# Arduino_PCD8544.net
KiCad netlist of a schematic drawn in EAGLE
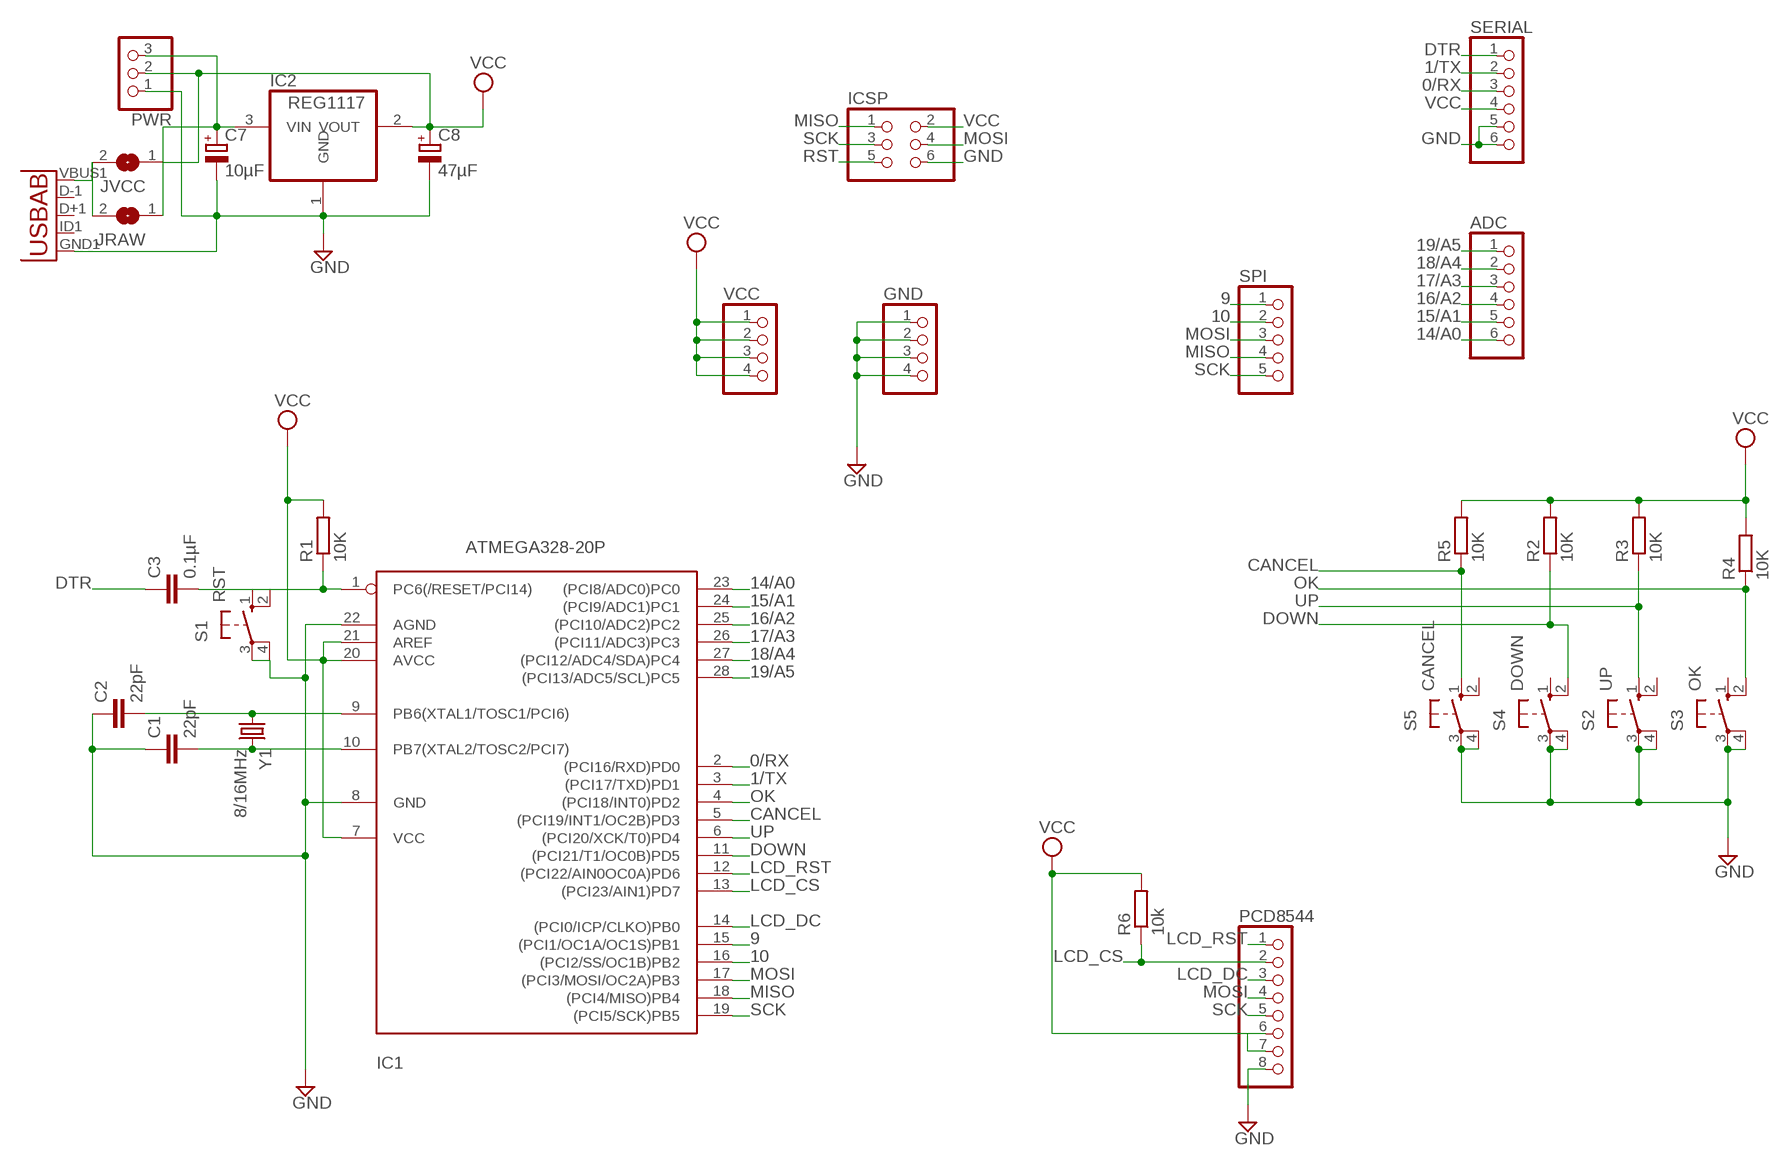
[diagram p0: schematic, sheet 1]

(export (version "E")
  (design (tool "Eeschema 10.0.6"))
  (components
    (comp (ref "ADC")
      (value "PINHD-1X6")
      (footprint "eagle-import:1X06")
      (libsource (lib "eagle-import") (part "PINHD-1X6"))
    )
    (comp (ref "C1")
      (value "22pF")
      (footprint "eagle-import:C0805")
      (libsource (lib "eagle-import") (part "C-EUC0805"))
    )
    (comp (ref "C2")
      (value "22pF")
      (footprint "eagle-import:C0805")
      (libsource (lib "eagle-import") (part "C-EUC0805"))
    )
    (comp (ref "C3")
      (value "0.1µF")
      (footprint "eagle-import:C0805")
      (libsource (lib "eagle-import") (part "C-EUC0805"))
    )
    (comp (ref "C7")
      (value "10µF")
      (footprint "eagle-import:E2,5-5")
      (libsource (lib "eagle-import") (part "CPOL-EUE2.5-5"))
    )
    (comp (ref "C8")
      (value "47µF")
      (footprint "eagle-import:E2,5-5")
      (libsource (lib "eagle-import") (part "CPOL-EUE2.5-5"))
    )
    (comp (ref "GND")
      (value "PINHD-1X4")
      (footprint "eagle-import:1X04")
      (libsource (lib "eagle-import") (part "PINHD-1X4"))
    )
    (comp (ref "IC1")
      (value "ATMEGA328-20P")
      (footprint "eagle-import:DIL28-3")
      (libsource (lib "eagle-import") (part "ATMEGA328P-20"))
    )
    (comp (ref "IC2")
      (value "REG1117")
      (footprint "eagle-import:SOT223")
      (libsource (lib "eagle-import") (part "REG1117"))
    )
    (comp (ref "ICSP")
      (value "PINHD-2X3")
      (footprint "eagle-import:2X03")
      (libsource (lib "eagle-import") (part "PINHD-2X3"))
    )
    (comp (ref "JRAW")
      (value "SJ")
      (footprint "eagle-import:SJ")
      (libsource (lib "eagle-import") (part "SJ"))
    )
    (comp (ref "JVCC")
      (value "SJ")
      (footprint "eagle-import:SJ")
      (libsource (lib "eagle-import") (part "SJ"))
    )
    (comp (ref "PCD8544")
      (value "PINHD-1X8")
      (footprint "eagle-import:1X08")
      (libsource (lib "eagle-import") (part "PINHD-1X8"))
    )
    (comp (ref "PWR")
      (value "PINHD-1X3")
      (footprint "eagle-import:1X03")
      (libsource (lib "eagle-import") (part "PINHD-1X3"))
    )
    (comp (ref "R1")
      (value "10K")
      (footprint "eagle-import:R0805")
      (libsource (lib "eagle-import") (part "R-EU_R0805"))
    )
    (comp (ref "R2")
      (value "10K")
      (footprint "eagle-import:R0805")
      (libsource (lib "eagle-import") (part "resistor_R-EU_R0805"))
    )
    (comp (ref "R3")
      (value "10K")
      (footprint "eagle-import:R0805")
      (libsource (lib "eagle-import") (part "resistor_R-EU_R0805"))
    )
    (comp (ref "R4")
      (value "10K")
      (footprint "eagle-import:R0805")
      (libsource (lib "eagle-import") (part "resistor_R-EU_R0805"))
    )
    (comp (ref "R5")
      (value "10K")
      (footprint "eagle-import:R0805")
      (libsource (lib "eagle-import") (part "resistor_R-EU_R0805"))
    )
    (comp (ref "R6")
      (value "10k")
      (footprint "eagle-import:R0805")
      (libsource (lib "eagle-import") (part "resistor_R-EU_R0805"))
    )
    (comp (ref "S1")
      (value "RST")
      (footprint "eagle-import:B3F-10XX")
      (fields (field (name "MPN") "B3F-1000"))
      (libsource (lib "eagle-import") (part "10-XX"))
    )
    (comp (ref "S2")
      (value "UP")
      (footprint "eagle-import:B3F-10XX")
      (fields (field (name "MPN") "B3F-1000"))
      (libsource (lib "eagle-import") (part "10-XX"))
    )
    (comp (ref "S3")
      (value "OK")
      (footprint "eagle-import:B3F-10XX")
      (fields (field (name "MPN") "B3F-1000"))
      (libsource (lib "eagle-import") (part "10-XX"))
    )
    (comp (ref "S4")
      (value "DOWN")
      (footprint "eagle-import:B3F-10XX")
      (fields (field (name "MPN") "B3F-1000"))
      (libsource (lib "eagle-import") (part "10-XX"))
    )
    (comp (ref "S5")
      (value "CANCEL")
      (footprint "eagle-import:B3F-10XX")
      (fields (field (name "MPN") "B3F-1000"))
      (libsource (lib "eagle-import") (part "10-XX"))
    )
    (comp (ref "SERIAL")
      (value "PINHD-1X6")
      (footprint "eagle-import:1X06")
      (libsource (lib "eagle-import") (part "PINHD-1X6"))
    )
    (comp (ref "SPI")
      (value "PINHD-1X5")
      (footprint "eagle-import:1X05")
      (libsource (lib "eagle-import") (part "PINHD-1X5"))
    )
    (comp (ref "U1")
      (value "USB\"\"")
      (footprint "eagle-import:USB-MICRO-SMD")
      (libsource (lib "eagle-import") (part "USB{dblquote}{dblquote}"))
    )
    (comp (ref "VCC")
      (value "PINHD-1X4")
      (footprint "eagle-import:1X04")
      (libsource (lib "eagle-import") (part "PINHD-1X4"))
    )
    (comp (ref "Y1")
      (value "8/16MHz")
      (footprint "eagle-import:HC49US")
      (libsource (lib "eagle-import") (part "CRYSTALHC49US"))
    )
  )
  (nets
    (net (code "1") (name "/0{slash}RX") (class "Default")
      (node (ref "IC1") (pin "2") (pinfunction "(PCI16/RXD)PD0_2") (pintype "bidirectional"))
      (node (ref "SERIAL") (pin "3") (pinfunction "3_3") (pintype "passive"))
    )
    (net (code "2") (name "/1{slash}TX") (class "Default")
      (node (ref "IC1") (pin "3") (pinfunction "(PCI17/TXD)PD1_3") (pintype "bidirectional"))
      (node (ref "SERIAL") (pin "2") (pinfunction "2_2") (pintype "passive"))
    )
    (net (code "3") (name "/9") (class "Default")
      (node (ref "IC1") (pin "15") (pinfunction "(PCI1/OC1A/OC1S)PB1_15") (pintype "bidirectional"))
      (node (ref "SPI") (pin "1") (pinfunction "1_1") (pintype "passive"))
    )
    (net (code "4") (name "/10") (class "Default")
      (node (ref "IC1") (pin "16") (pinfunction "(PCI2/SS/OC1B)PB2_16") (pintype "bidirectional"))
      (node (ref "SPI") (pin "2") (pinfunction "2_2") (pintype "passive"))
    )
    (net (code "5") (name "/14{slash}A0") (class "Default")
      (node (ref "ADC") (pin "6") (pinfunction "6_6") (pintype "passive"))
      (node (ref "IC1") (pin "23") (pinfunction "(PCI8/ADC0)PC0_23") (pintype "bidirectional"))
    )
    (net (code "6") (name "/15{slash}A1") (class "Default")
      (node (ref "ADC") (pin "5") (pinfunction "5_5") (pintype "passive"))
      (node (ref "IC1") (pin "24") (pinfunction "(PCI9/ADC1)PC1_24") (pintype "bidirectional"))
    )
    (net (code "7") (name "/16{slash}A2") (class "Default")
      (node (ref "ADC") (pin "4") (pinfunction "4_4") (pintype "passive"))
      (node (ref "IC1") (pin "25") (pinfunction "(PCI10/ADC2)PC2_25") (pintype "bidirectional"))
    )
    (net (code "8") (name "/17{slash}A3") (class "Default")
      (node (ref "ADC") (pin "3") (pinfunction "3_3") (pintype "passive"))
      (node (ref "IC1") (pin "26") (pinfunction "(PCI11/ADC3)PC3_26") (pintype "bidirectional"))
    )
    (net (code "9") (name "/18{slash}A4") (class "Default")
      (node (ref "ADC") (pin "2") (pinfunction "2_2") (pintype "passive"))
      (node (ref "IC1") (pin "27") (pinfunction "(PCI12/ADC4/SDA)PC4_27") (pintype "bidirectional"))
    )
    (net (code "10") (name "/19{slash}A5") (class "Default")
      (node (ref "ADC") (pin "1") (pinfunction "1_1") (pintype "passive"))
      (node (ref "IC1") (pin "28") (pinfunction "(PCI13/ADC5/SCL)PC5_28") (pintype "bidirectional"))
    )
    (net (code "11") (name "/CANCEL") (class "Default")
      (node (ref "IC1") (pin "5") (pinfunction "(PCI19/INT1/OC2B)PD3_5") (pintype "bidirectional"))
      (node (ref "R5") (pin "1") (pinfunction "1_1") (pintype "passive"))
      (node (ref "S5") (pin "1") (pinfunction "S_1") (pintype "passive"))
    )
    (net (code "12") (name "/DOWN") (class "Default")
      (node (ref "IC1") (pin "11") (pinfunction "(PCI21/T1/OC0B)PD5_11") (pintype "bidirectional"))
      (node (ref "R2") (pin "1") (pinfunction "1_1") (pintype "passive"))
      (node (ref "S4") (pin "2") (pinfunction "S1_2") (pintype "passive"))
    )
    (net (code "13") (name "/DTR") (class "Default")
      (node (ref "C3") (pin "1") (pinfunction "1_1") (pintype "passive"))
      (node (ref "SERIAL") (pin "1") (pinfunction "1_1") (pintype "passive"))
    )
    (net (code "14") (name "/LCD_CS") (class "Default")
      (node (ref "IC1") (pin "13") (pinfunction "(PCI23/AIN1)PD7_13") (pintype "bidirectional"))
      (node (ref "PCD8544") (pin "2") (pinfunction "2_2") (pintype "passive"))
      (node (ref "R6") (pin "1") (pinfunction "1_1") (pintype "passive"))
    )
    (net (code "15") (name "/LCD_DC") (class "Default")
      (node (ref "IC1") (pin "14") (pinfunction "(PCI0/ICP/CLKO)PB0_14") (pintype "bidirectional"))
      (node (ref "PCD8544") (pin "3") (pinfunction "3_3") (pintype "passive"))
    )
    (net (code "16") (name "/LCD_RST") (class "Default")
      (node (ref "IC1") (pin "12") (pinfunction "(PCI22/AIN0OC0A)PD6_12") (pintype "bidirectional"))
      (node (ref "PCD8544") (pin "1") (pinfunction "1_1") (pintype "passive"))
    )
    (net (code "17") (name "/MISO") (class "Default")
      (node (ref "IC1") (pin "18") (pinfunction "(PCI4/MISO)PB4_18") (pintype "bidirectional"))
      (node (ref "ICSP") (pin "1") (pinfunction "1_1") (pintype "passive"))
      (node (ref "SPI") (pin "4") (pinfunction "4_4") (pintype "passive"))
    )
    (net (code "18") (name "/MOSI") (class "Default")
      (node (ref "IC1") (pin "17") (pinfunction "(PCI3/MOSI/OC2A)PB3_17") (pintype "bidirectional"))
      (node (ref "ICSP") (pin "4") (pinfunction "4_4") (pintype "passive"))
      (node (ref "PCD8544") (pin "4") (pinfunction "4_4") (pintype "passive"))
      (node (ref "SPI") (pin "3") (pinfunction "3_3") (pintype "passive"))
    )
    (net (code "19") (name "/OK") (class "Default")
      (node (ref "IC1") (pin "4") (pinfunction "(PCI18/INT0)PD2_4") (pintype "bidirectional"))
      (node (ref "R4") (pin "1") (pinfunction "1_1") (pintype "passive"))
      (node (ref "S3") (pin "2") (pinfunction "S1_2") (pintype "passive"))
    )
    (net (code "20") (name "/RST") (class "Default")
      (node (ref "C3") (pin "2") (pinfunction "2_2") (pintype "passive"))
      (node (ref "IC1") (pin "1") (pinfunction "PC6(/RESET/PCI14)_1") (pintype "bidirectional"))
      (node (ref "ICSP") (pin "5") (pinfunction "5_5") (pintype "passive"))
      (node (ref "R1") (pin "1") (pinfunction "1_1") (pintype "passive"))
      (node (ref "S1") (pin "1") (pinfunction "S_1") (pintype "passive"))
      (node (ref "S1") (pin "2") (pinfunction "S1_2") (pintype "passive"))
    )
    (net (code "21") (name "/SCK") (class "Default")
      (node (ref "IC1") (pin "19") (pinfunction "(PCI5/SCK)PB5_19") (pintype "bidirectional"))
      (node (ref "ICSP") (pin "3") (pinfunction "3_3") (pintype "passive"))
      (node (ref "PCD8544") (pin "5") (pinfunction "5_5") (pintype "passive"))
      (node (ref "SPI") (pin "5") (pinfunction "5_5") (pintype "passive"))
    )
    (net (code "22") (name "/UP") (class "Default")
      (node (ref "IC1") (pin "6") (pinfunction "(PCI20/XCK/T0)PD4_6") (pintype "bidirectional"))
      (node (ref "R3") (pin "1") (pinfunction "1_1") (pintype "passive"))
      (node (ref "S2") (pin "1") (pinfunction "S_1") (pintype "passive"))
    )
    (net (code "23") (name "GND") (class "Default")
      (node (ref "C1") (pin "1") (pinfunction "1_1") (pintype "passive"))
      (node (ref "C2") (pin "1") (pinfunction "1_1") (pintype "passive"))
      (node (ref "C7") (pin "-") (pinfunction "-_-") (pintype "passive"))
      (node (ref "C8") (pin "-") (pinfunction "-_-") (pintype "passive"))
      (node (ref "GND") (pin "1") (pinfunction "1_1") (pintype "passive"))
      (node (ref "GND") (pin "2") (pinfunction "2_2") (pintype "passive"))
      (node (ref "GND") (pin "3") (pinfunction "3_3") (pintype "passive"))
      (node (ref "GND") (pin "4") (pinfunction "4_4") (pintype "passive"))
      (node (ref "IC1") (pin "22") (pinfunction "AGND_22") (pintype "bidirectional"))
      (node (ref "IC1") (pin "8") (pinfunction "GND_8") (pintype "bidirectional"))
      (node (ref "IC2") (pin "1") (pinfunction "GND_1") (pintype "power_in"))
      (node (ref "ICSP") (pin "6") (pinfunction "6_6") (pintype "passive"))
      (node (ref "PCD8544") (pin "8") (pinfunction "8_8") (pintype "passive"))
      (node (ref "PWR") (pin "1") (pinfunction "1_1") (pintype "passive"))
      (node (ref "S1") (pin "3") (pinfunction "P_3") (pintype "passive"))
      (node (ref "S1") (pin "4") (pinfunction "P1_4") (pintype "passive"))
      (node (ref "S2") (pin "3") (pinfunction "P_3") (pintype "passive"))
      (node (ref "S2") (pin "4") (pinfunction "P1_4") (pintype "passive"))
      (node (ref "S3") (pin "3") (pinfunction "P_3") (pintype "passive"))
      (node (ref "S3") (pin "4") (pinfunction "P1_4") (pintype "passive"))
      (node (ref "S4") (pin "3") (pinfunction "P_3") (pintype "passive"))
      (node (ref "S4") (pin "4") (pinfunction "P1_4") (pintype "passive"))
      (node (ref "S5") (pin "3") (pinfunction "P_3") (pintype "passive"))
      (node (ref "S5") (pin "4") (pinfunction "P1_4") (pintype "passive"))
      (node (ref "SERIAL") (pin "5") (pinfunction "5_5") (pintype "passive"))
      (node (ref "SERIAL") (pin "6") (pinfunction "6_6") (pintype "passive"))
      (node (ref "U1") (pin "GND1") (pinfunction "GND_GND1") (pintype "bidirectional"))
    )
    (net (code "24") (name "Net-(IC1-PB6(XTAL1{slash}TOSC1{slash}PCI6))") (class "Default")
      (node (ref "C2") (pin "2") (pinfunction "2_2") (pintype "passive"))
      (node (ref "IC1") (pin "9") (pinfunction "PB6(XTAL1/TOSC1/PCI6)_9") (pintype "bidirectional"))
      (node (ref "Y1") (pin "1") (pinfunction "1_1") (pintype "passive"))
    )
    (net (code "25") (name "Net-(IC1-PB7(XTAL2{slash}TOSC2{slash}PCI7))") (class "Default")
      (node (ref "C1") (pin "2") (pinfunction "2_2") (pintype "passive"))
      (node (ref "IC1") (pin "10") (pinfunction "PB7(XTAL2/TOSC2/PCI7)_10") (pintype "bidirectional"))
      (node (ref "Y1") (pin "2") (pinfunction "2_2") (pintype "passive"))
    )
    (net (code "26") (name "Net-(IC2-VIN)") (class "Default")
      (node (ref "C7") (pin "+") (pinfunction "+_+") (pintype "passive"))
      (node (ref "IC2") (pin "3") (pinfunction "VIN_3") (pintype "input"))
      (node (ref "JRAW") (pin "1") (pinfunction "1_1") (pintype "passive"))
      (node (ref "PWR") (pin "3") (pinfunction "3_3") (pintype "passive"))
    )
    (net (code "27") (name "Net-(U1-VBUS)") (class "Default")
      (node (ref "JRAW") (pin "2") (pinfunction "2_2") (pintype "passive"))
      (node (ref "JVCC") (pin "2") (pinfunction "2_2") (pintype "passive"))
      (node (ref "U1") (pin "VBUS1") (pinfunction "VBUS_VBUS1") (pintype "bidirectional"))
    )
    (net (code "28") (name "VCC") (class "Default")
      (node (ref "C8") (pin "+") (pinfunction "+_+") (pintype "passive"))
      (node (ref "IC1") (pin "20") (pinfunction "AVCC_20") (pintype "bidirectional"))
      (node (ref "IC1") (pin "21") (pinfunction "AREF_21") (pintype "bidirectional"))
      (node (ref "IC1") (pin "7") (pinfunction "VCC_7") (pintype "bidirectional"))
      (node (ref "IC2") (pin "2") (pinfunction "VOUT_2") (pintype "output"))
      (node (ref "ICSP") (pin "2") (pinfunction "2_2") (pintype "passive"))
      (node (ref "JVCC") (pin "1") (pinfunction "1_1") (pintype "passive"))
      (node (ref "PCD8544") (pin "6") (pinfunction "6_6") (pintype "passive"))
      (node (ref "PCD8544") (pin "7") (pinfunction "7_7") (pintype "passive"))
      (node (ref "PWR") (pin "2") (pinfunction "2_2") (pintype "passive"))
      (node (ref "R1") (pin "2") (pinfunction "2_2") (pintype "passive"))
      (node (ref "R2") (pin "2") (pinfunction "2_2") (pintype "passive"))
      (node (ref "R3") (pin "2") (pinfunction "2_2") (pintype "passive"))
      (node (ref "R4") (pin "2") (pinfunction "2_2") (pintype "passive"))
      (node (ref "R5") (pin "2") (pinfunction "2_2") (pintype "passive"))
      (node (ref "R6") (pin "2") (pinfunction "2_2") (pintype "passive"))
      (node (ref "SERIAL") (pin "4") (pinfunction "4_4") (pintype "passive"))
      (node (ref "VCC") (pin "1") (pinfunction "1_1") (pintype "passive"))
      (node (ref "VCC") (pin "2") (pinfunction "2_2") (pintype "passive"))
      (node (ref "VCC") (pin "3") (pinfunction "3_3") (pintype "passive"))
      (node (ref "VCC") (pin "4") (pinfunction "4_4") (pintype "passive"))
    )
    (net (code "29") (name "unconnected-(S2-S1-Pad2)") (class "Default")
      (node (ref "S2") (pin "2") (pinfunction "S1_2") (pintype "passive"))
    )
    (net (code "30") (name "unconnected-(S3-S-Pad1)") (class "Default")
      (node (ref "S3") (pin "1") (pinfunction "S_1") (pintype "passive"))
    )
    (net (code "31") (name "unconnected-(S4-S-Pad1)") (class "Default")
      (node (ref "S4") (pin "1") (pinfunction "S_1") (pintype "passive"))
    )
    (net (code "32") (name "unconnected-(S5-S1-Pad2)") (class "Default")
      (node (ref "S5") (pin "2") (pinfunction "S1_2") (pintype "passive"))
    )
    (net (code "33") (name "unconnected-(U1-D+-PadD+1)") (class "Default")
      (node (ref "U1") (pin "D+1") (pinfunction "D+_D+1") (pintype "bidirectional"))
    )
    (net (code "34") (name "unconnected-(U1-D--PadD-1)") (class "Default")
      (node (ref "U1") (pin "D-1") (pinfunction "D-_D-1") (pintype "bidirectional"))
    )
    (net (code "35") (name "unconnected-(U1-USBID-PadID1)") (class "Default")
      (node (ref "U1") (pin "ID1") (pinfunction "USBID_ID1") (pintype "bidirectional"))
    )
  )
)
